# main.net
KiCad netlist of a schematic drawn in EAGLE
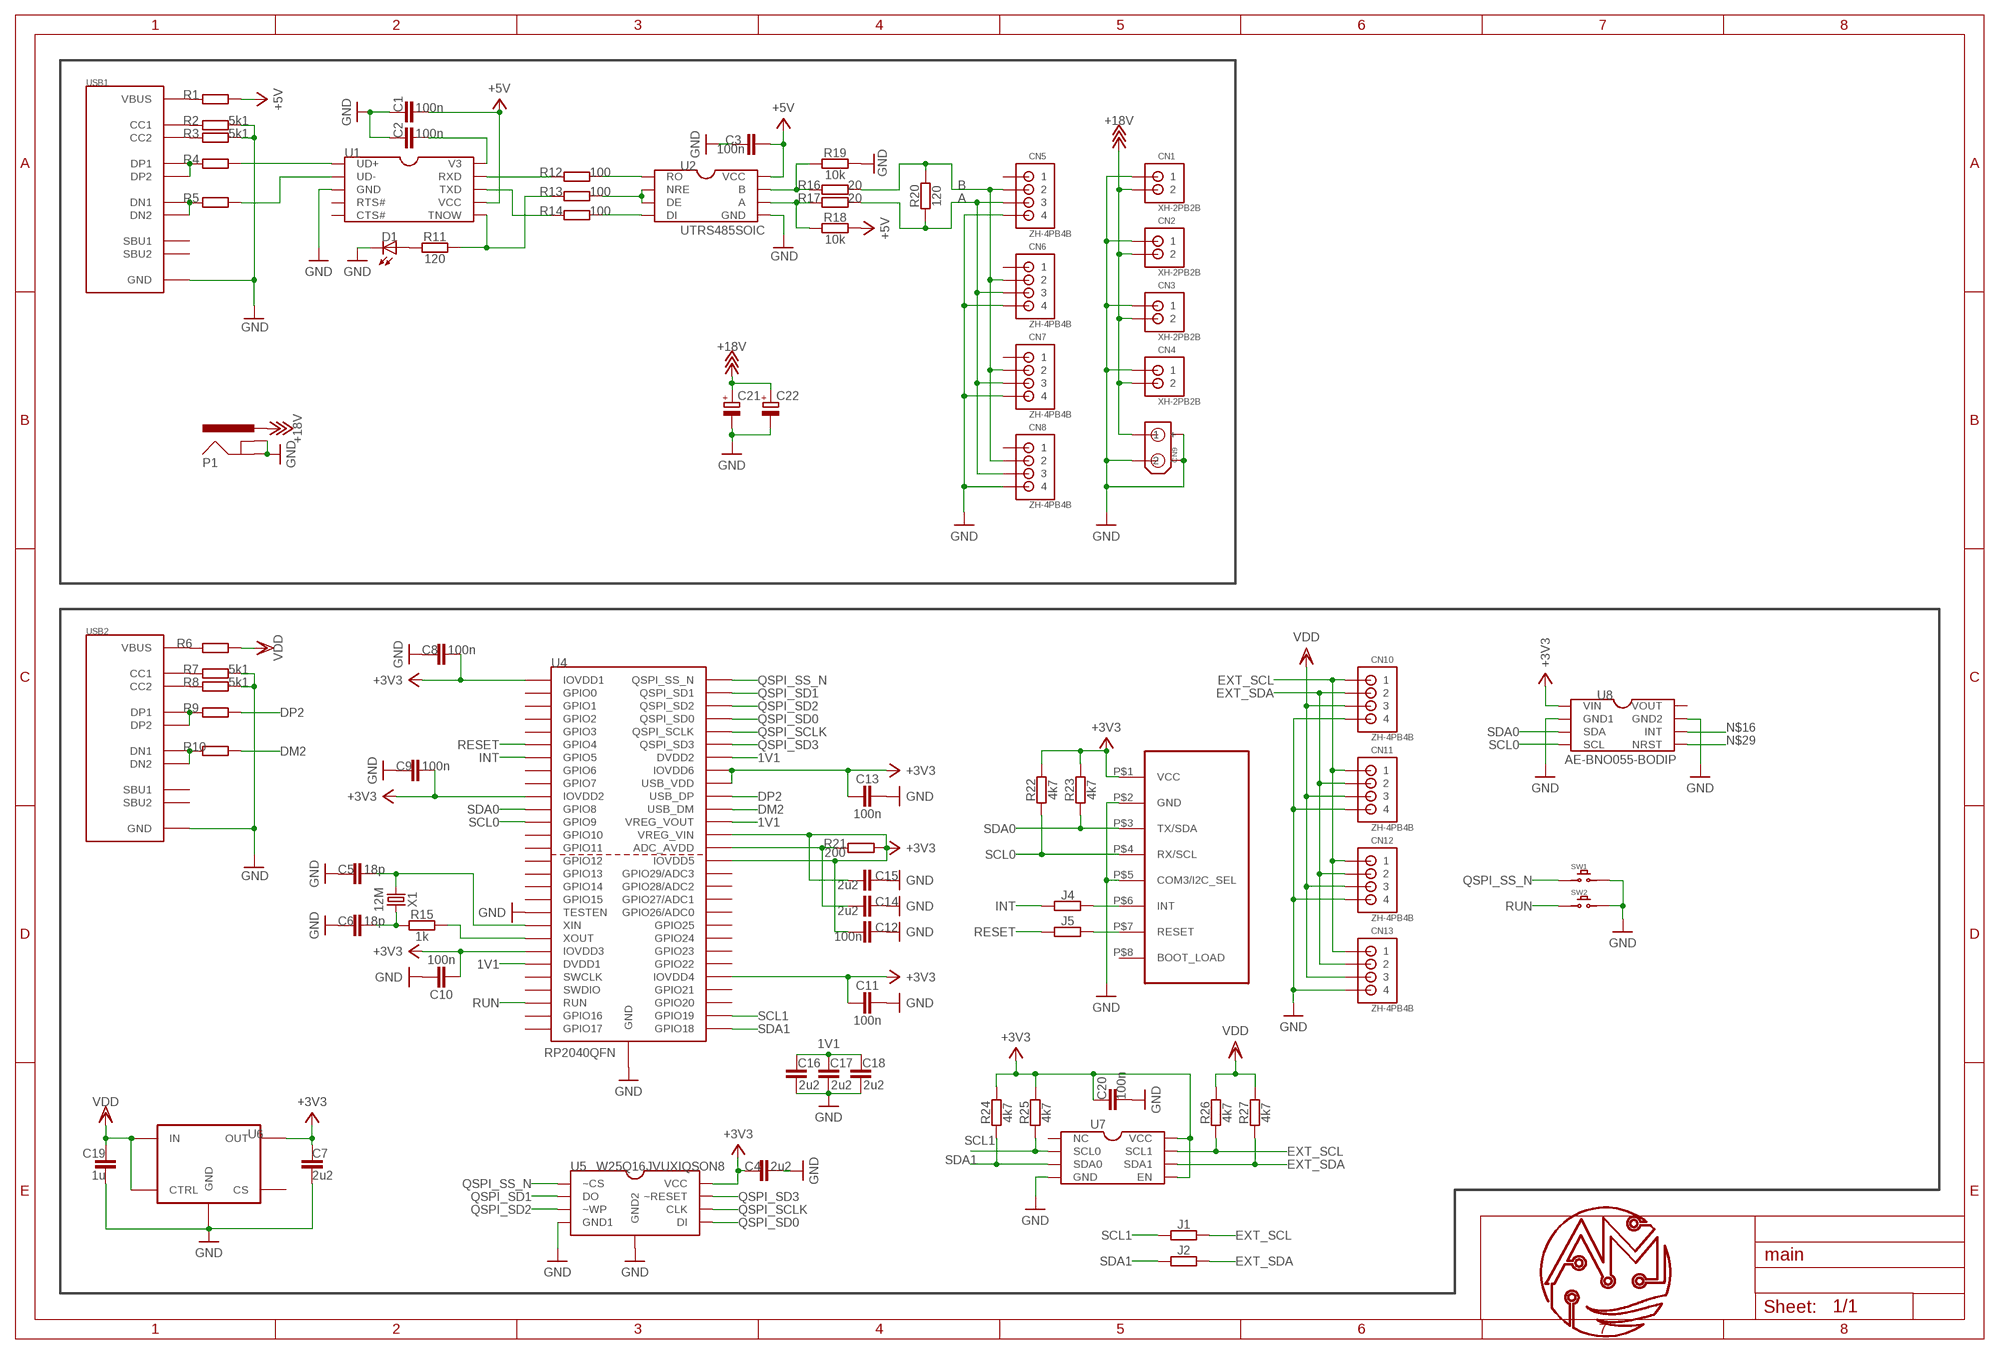
[diagram p0: schematic, sheet 1]

(export (version "E")
  (design (tool "Eeschema 10.0.6"))
  (components
    (comp (ref "C1")
      (value "100n")
      (footprint "eagle-import:C1608")
      (libsource (lib "eagle-import") (part "CAPACITOR1608"))
    )
    (comp (ref "C2")
      (value "100n")
      (footprint "eagle-import:C1608")
      (libsource (lib "eagle-import") (part "CAPACITOR1608"))
    )
    (comp (ref "C3")
      (value "100n")
      (footprint "eagle-import:C1608")
      (libsource (lib "eagle-import") (part "CAPACITOR1608"))
    )
    (comp (ref "C4")
      (value "2u2")
      (footprint "eagle-import:C1608")
      (libsource (lib "eagle-import") (part "CAPACITOR1608"))
    )
    (comp (ref "C5")
      (value "18p")
      (footprint "eagle-import:C1608")
      (libsource (lib "eagle-import") (part "CAPACITOR1608"))
    )
    (comp (ref "C6")
      (value "18p")
      (footprint "eagle-import:C1608")
      (libsource (lib "eagle-import") (part "CAPACITOR1608"))
    )
    (comp (ref "C7")
      (value "2u2")
      (footprint "eagle-import:C1608")
      (libsource (lib "eagle-import") (part "CAPACITOR1608"))
    )
    (comp (ref "C8")
      (value "100n")
      (footprint "eagle-import:C1608")
      (libsource (lib "eagle-import") (part "CAPACITOR1608"))
    )
    (comp (ref "C9")
      (value "100n")
      (footprint "eagle-import:C1608")
      (libsource (lib "eagle-import") (part "CAPACITOR1608"))
    )
    (comp (ref "C10")
      (value "100n")
      (footprint "eagle-import:C1608")
      (libsource (lib "eagle-import") (part "CAPACITOR1608"))
    )
    (comp (ref "C11")
      (value "100n")
      (footprint "eagle-import:C1608")
      (libsource (lib "eagle-import") (part "CAPACITOR1608"))
    )
    (comp (ref "C12")
      (value "100n")
      (footprint "eagle-import:C1608")
      (libsource (lib "eagle-import") (part "CAPACITOR1608"))
    )
    (comp (ref "C13")
      (value "100n")
      (footprint "eagle-import:C1608")
      (libsource (lib "eagle-import") (part "CAPACITOR1608"))
    )
    (comp (ref "C14")
      (value "2u2")
      (footprint "eagle-import:C1608")
      (libsource (lib "eagle-import") (part "CAPACITOR1608"))
    )
    (comp (ref "C15")
      (value "2u2")
      (footprint "eagle-import:C1608")
      (libsource (lib "eagle-import") (part "CAPACITOR1608"))
    )
    (comp (ref "C16")
      (value "2u2")
      (footprint "eagle-import:C1608")
      (libsource (lib "eagle-import") (part "CAPACITOR1608"))
    )
    (comp (ref "C17")
      (value "2u2")
      (footprint "eagle-import:C1608")
      (libsource (lib "eagle-import") (part "CAPACITOR1608"))
    )
    (comp (ref "C18")
      (value "2u2")
      (footprint "eagle-import:C1608")
      (libsource (lib "eagle-import") (part "CAPACITOR1608"))
    )
    (comp (ref "C19")
      (value "1u")
      (footprint "eagle-import:C1608")
      (libsource (lib "eagle-import") (part "CAPACITOR1608"))
    )
    (comp (ref "C20")
      (value "100n")
      (footprint "eagle-import:C1608")
      (libsource (lib "eagle-import") (part "CAPACITOR1608"))
    )
    (comp (ref "C21")
      (value "E_CAPACITORRADIAL_D8")
      (footprint "eagle-import:ECAP-D80-L115")
      (libsource (lib "eagle-import") (part "E_CAPACITORRADIAL_D8"))
    )
    (comp (ref "C22")
      (value "E_CAPACITORRADIAL_D8")
      (footprint "eagle-import:ECAP-D80-L115")
      (libsource (lib "eagle-import") (part "E_CAPACITORRADIAL_D8"))
    )
    (comp (ref "CN1")
      (value "XH-2PB2B")
      (footprint "eagle-import:B2B-XH-A")
      (libsource (lib "eagle-import") (part "XH-2PB2B"))
    )
    (comp (ref "CN2")
      (value "XH-2PB2B")
      (footprint "eagle-import:B2B-XH-A")
      (libsource (lib "eagle-import") (part "XH-2PB2B"))
    )
    (comp (ref "CN3")
      (value "XH-2PB2B")
      (footprint "eagle-import:B2B-XH-A")
      (libsource (lib "eagle-import") (part "XH-2PB2B"))
    )
    (comp (ref "CN4")
      (value "XH-2PB2B")
      (footprint "eagle-import:B2B-XH-A")
      (libsource (lib "eagle-import") (part "XH-2PB2B"))
    )
    (comp (ref "CN5")
      (value "ZH-4PB4B")
      (footprint "eagle-import:B4B-ZR")
      (libsource (lib "eagle-import") (part "ZH-4PB4B"))
    )
    (comp (ref "CN6")
      (value "ZH-4PB4B")
      (footprint "eagle-import:B4B-ZR")
      (libsource (lib "eagle-import") (part "ZH-4PB4B"))
    )
    (comp (ref "CN7")
      (value "ZH-4PB4B")
      (footprint "eagle-import:B4B-ZR")
      (libsource (lib "eagle-import") (part "ZH-4PB4B"))
    )
    (comp (ref "CN8")
      (value "ZH-4PB4B")
      (footprint "eagle-import:B4B-ZR")
      (libsource (lib "eagle-import") (part "ZH-4PB4B"))
    )
    (comp (ref "CN9")
      (value "XT60PW-MPCB")
      (footprint "eagle-import:XT60PW-M")
      (libsource (lib "eagle-import") (part "XT60PW-MPCB"))
    )
    (comp (ref "CN10")
      (value "ZH-4PB4B")
      (footprint "eagle-import:B4B-ZR")
      (libsource (lib "eagle-import") (part "ZH-4PB4B"))
    )
    (comp (ref "CN11")
      (value "ZH-4PB4B")
      (footprint "eagle-import:B4B-ZR")
      (libsource (lib "eagle-import") (part "ZH-4PB4B"))
    )
    (comp (ref "CN12")
      (value "ZH-4PB4B")
      (footprint "eagle-import:B4B-ZR")
      (libsource (lib "eagle-import") (part "ZH-4PB4B"))
    )
    (comp (ref "CN13")
      (value "ZH-4PB4B")
      (footprint "eagle-import:B4B-ZR")
      (libsource (lib "eagle-import") (part "ZH-4PB4B"))
    )
    (comp (ref "D1")
      (value "LED1608R")
      (footprint "eagle-import:LED1608R")
      (libsource (lib "eagle-import") (part "LED1608R"))
    )
    (comp (ref "J1")
      (value "JUMPER1608")
      (footprint "eagle-import:J1608")
      (libsource (lib "eagle-import") (part "JUMPER1608"))
    )
    (comp (ref "J2")
      (value "JUMPER1608")
      (footprint "eagle-import:J1608")
      (libsource (lib "eagle-import") (part "JUMPER1608"))
    )
    (comp (ref "J4")
      (value "JUMPER1608")
      (footprint "eagle-import:J1608")
      (libsource (lib "eagle-import") (part "JUMPER1608"))
    )
    (comp (ref "J5")
      (value "JUMPER1608")
      (footprint "eagle-import:J1608")
      (libsource (lib "eagle-import") (part "JUMPER1608"))
    )
    (comp (ref "P1")
      (value "DC-JACKMJ179PH")
      (footprint "eagle-import:MJ179PH")
      (libsource (lib "eagle-import") (part "DC-JACKMJ179PH"))
    )
    (comp (ref "R1")
      (value "RESISTER3225")
      (footprint "eagle-import:R3225")
      (libsource (lib "eagle-import") (part "RESISTER3225"))
    )
    (comp (ref "R2")
      (value "5k1")
      (footprint "eagle-import:R1608")
      (libsource (lib "eagle-import") (part "RESISTER1608"))
    )
    (comp (ref "R3")
      (value "5k1")
      (footprint "eagle-import:R1608")
      (libsource (lib "eagle-import") (part "RESISTER1608"))
    )
    (comp (ref "R4")
      (value "RESISTER1608")
      (footprint "eagle-import:R1608")
      (libsource (lib "eagle-import") (part "RESISTER1608"))
    )
    (comp (ref "R5")
      (value "RESISTER1608")
      (footprint "eagle-import:R1608")
      (libsource (lib "eagle-import") (part "RESISTER1608"))
    )
    (comp (ref "R6")
      (value "RESISTER3225")
      (footprint "eagle-import:R3225")
      (libsource (lib "eagle-import") (part "RESISTER3225"))
    )
    (comp (ref "R7")
      (value "5k1")
      (footprint "eagle-import:R1608")
      (libsource (lib "eagle-import") (part "RESISTER1608"))
    )
    (comp (ref "R8")
      (value "5k1")
      (footprint "eagle-import:R1608")
      (libsource (lib "eagle-import") (part "RESISTER1608"))
    )
    (comp (ref "R9")
      (value "RESISTER1608")
      (footprint "eagle-import:R1608")
      (libsource (lib "eagle-import") (part "RESISTER1608"))
    )
    (comp (ref "R10")
      (value "RESISTER1608")
      (footprint "eagle-import:R1608")
      (libsource (lib "eagle-import") (part "RESISTER1608"))
    )
    (comp (ref "R11")
      (value "120")
      (footprint "eagle-import:R1608")
      (libsource (lib "eagle-import") (part "RESISTER1608"))
    )
    (comp (ref "R12")
      (value "100")
      (footprint "eagle-import:R1608")
      (libsource (lib "eagle-import") (part "RESISTER1608"))
    )
    (comp (ref "R13")
      (value "100")
      (footprint "eagle-import:R1608")
      (libsource (lib "eagle-import") (part "RESISTER1608"))
    )
    (comp (ref "R14")
      (value "100")
      (footprint "eagle-import:R1608")
      (libsource (lib "eagle-import") (part "RESISTER1608"))
    )
    (comp (ref "R15")
      (value "1k")
      (footprint "eagle-import:R1608")
      (libsource (lib "eagle-import") (part "RESISTER1608"))
    )
    (comp (ref "R16")
      (value "20")
      (footprint "eagle-import:R1608")
      (libsource (lib "eagle-import") (part "RESISTER1608"))
    )
    (comp (ref "R17")
      (value "20")
      (footprint "eagle-import:R1608")
      (libsource (lib "eagle-import") (part "RESISTER1608"))
    )
    (comp (ref "R18")
      (value "10k")
      (footprint "eagle-import:R1608")
      (libsource (lib "eagle-import") (part "RESISTER1608"))
    )
    (comp (ref "R19")
      (value "10k")
      (footprint "eagle-import:R1608")
      (libsource (lib "eagle-import") (part "RESISTER1608"))
    )
    (comp (ref "R20")
      (value "120")
      (footprint "eagle-import:R1608")
      (libsource (lib "eagle-import") (part "RESISTER1608"))
    )
    (comp (ref "R21")
      (value "200")
      (footprint "eagle-import:R1608")
      (libsource (lib "eagle-import") (part "RESISTER1608"))
    )
    (comp (ref "R22")
      (value "4k7")
      (footprint "eagle-import:R1608")
      (libsource (lib "eagle-import") (part "RESISTER1608"))
    )
    (comp (ref "R23")
      (value "4k7")
      (footprint "eagle-import:R1608")
      (libsource (lib "eagle-import") (part "RESISTER1608"))
    )
    (comp (ref "R24")
      (value "4k7")
      (footprint "eagle-import:R1608")
      (libsource (lib "eagle-import") (part "RESISTER1608"))
    )
    (comp (ref "R25")
      (value "4k7")
      (footprint "eagle-import:R1608")
      (libsource (lib "eagle-import") (part "RESISTER1608"))
    )
    (comp (ref "R26")
      (value "4k7")
      (footprint "eagle-import:R1608")
      (libsource (lib "eagle-import") (part "RESISTER1608"))
    )
    (comp (ref "R27")
      (value "4k7")
      (footprint "eagle-import:R1608")
      (libsource (lib "eagle-import") (part "RESISTER1608"))
    )
    (comp (ref "SW1")
      (value "TSY3420SMD-HOLE")
      (footprint "eagle-import:TSY3420-HOLE")
      (libsource (lib "eagle-import") (part "TSY3420SMD-HOLE"))
    )
    (comp (ref "SW2")
      (value "TSY3420SMD-HOLE")
      (footprint "eagle-import:TSY3420-HOLE")
      (libsource (lib "eagle-import") (part "TSY3420SMD-HOLE"))
    )
    (comp (ref "U$2")
      (value "LOGO8MM")
      (footprint "eagle-import:LOGO-8MM")
      (libsource (lib "eagle-import") (part "LOGO8MM"))
    )
    (comp (ref "U1")
      (value "CH340EMSOP")
      (footprint "eagle-import:MSOP-05-10P")
      (libsource (lib "eagle-import") (part "CH340EMSOP"))
    )
    (comp (ref "U2")
      (value "UTRS485SOIC")
      (footprint "eagle-import:SOIC-8P")
      (libsource (lib "eagle-import") (part "UTRS485SOIC"))
    )
    (comp (ref "U3")
      (value "CJMCU-055SIP")
      (footprint "eagle-import:CJMCU-055")
      (libsource (lib "eagle-import") (part "CJMCU-055SIP"))
    )
    (comp (ref "U4")
      (value "RP2040QFN")
      (footprint "eagle-import:RP2040")
      (libsource (lib "eagle-import") (part "RP2040QFN"))
    )
    (comp (ref "U5")
      (value "W25Q16JVUXIQSON8")
      (footprint "eagle-import:W25Q16JVUXIQ")
      (libsource (lib "eagle-import") (part "W25Q16JVUXIQSON8"))
    )
    (comp (ref "U6")
      (value "REGULATOR2SOT23-5P")
      (footprint "eagle-import:SOT23-5P")
      (libsource (lib "eagle-import") (part "REGULATOR2SOT23-5P"))
    )
    (comp (ref "U7")
      (value "PCA9515SOIC")
      (footprint "eagle-import:PCA9515-SOIC")
      (libsource (lib "eagle-import") (part "PCA9515SOIC"))
    )
    (comp (ref "U8")
      (value "AE-BNO055-BODIP")
      (footprint "eagle-import:AE-BNO055-BO")
      (libsource (lib "eagle-import") (part "AE-BNO055-BODIP"))
    )
    (comp (ref "USB1")
      (value "USB-CSMD")
      (footprint "eagle-import:5077CR-16-SMC2-BK-TR")
      (libsource (lib "eagle-import") (part "USB-CSMD"))
    )
    (comp (ref "USB2")
      (value "USB-CSMD")
      (footprint "eagle-import:5077CR-16-SMC2-BK-TR")
      (libsource (lib "eagle-import") (part "USB-CSMD"))
    )
    (comp (ref "X1")
      (value "12M")
      (footprint "eagle-import:HC49S")
      (libsource (lib "eagle-import") (part "XTALHC49S"))
    )
  )
  (nets
    (net (code "1") (name "+3V3") (class "Default")
      (node (ref "C10") (pin "P$2") (pinfunction "2_P$2") (pintype "passive"))
      (node (ref "C11") (pin "P$2") (pinfunction "2_P$2") (pintype "passive"))
      (node (ref "C12") (pin "P$2") (pinfunction "2_P$2") (pintype "passive"))
      (node (ref "C13") (pin "P$1") (pinfunction "1_P$1") (pintype "passive"))
      (node (ref "C15") (pin "P$2") (pinfunction "2_P$2") (pintype "passive"))
      (node (ref "C20") (pin "P$1") (pinfunction "1_P$1") (pintype "passive"))
      (node (ref "C4") (pin "P$1") (pinfunction "1_P$1") (pintype "passive"))
      (node (ref "C7") (pin "P$2") (pinfunction "2_P$2") (pintype "passive"))
      (node (ref "C8") (pin "P$2") (pinfunction "2_P$2") (pintype "passive"))
      (node (ref "C9") (pin "P$2") (pinfunction "2_P$2") (pintype "passive"))
      (node (ref "R21") (pin "P$2") (pinfunction "2_P$2") (pintype "passive"))
      (node (ref "R22") (pin "P$2") (pinfunction "2_P$2") (pintype "passive"))
      (node (ref "R23") (pin "P$2") (pinfunction "2_P$2") (pintype "passive"))
      (node (ref "R24") (pin "P$2") (pinfunction "2_P$2") (pintype "passive"))
      (node (ref "R25") (pin "P$2") (pinfunction "2_P$2") (pintype "passive"))
      (node (ref "U3") (pin "P$1") (pinfunction "VCC_P$1") (pintype "bidirectional"))
      (node (ref "U4") (pin "P$1") (pinfunction "IOVDD1_P$1") (pintype "bidirectional"))
      (node (ref "U4") (pin "P$10") (pinfunction "IOVDD2_P$10") (pintype "bidirectional"))
      (node (ref "U4") (pin "P$22") (pinfunction "IOVDD3_P$22") (pintype "bidirectional"))
      (node (ref "U4") (pin "P$33") (pinfunction "IOVDD4_P$33") (pintype "bidirectional"))
      (node (ref "U4") (pin "P$42") (pinfunction "IOVDD5_P$42") (pintype "bidirectional"))
      (node (ref "U4") (pin "P$44") (pinfunction "VREG_VIN_P$44") (pintype "bidirectional"))
      (node (ref "U4") (pin "P$48") (pinfunction "USB_VDD_P$48") (pintype "bidirectional"))
      (node (ref "U4") (pin "P$49") (pinfunction "IOVDD6_P$49") (pintype "bidirectional"))
      (node (ref "U5") (pin "P$8") (pinfunction "VCC_P$8") (pintype "passive"))
      (node (ref "U6") (pin "P$5") (pinfunction "OUT_P$5") (pintype "passive"))
      (node (ref "U7") (pin "P$5") (pinfunction "EN_P$5") (pintype "passive"))
      (node (ref "U7") (pin "P$8") (pinfunction "VCC_P$8") (pintype "passive"))
      (node (ref "U8") (pin "P$1") (pinfunction "VIN_P$1") (pintype "passive"))
    )
    (net (code "2") (name "+5V") (class "Default")
      (node (ref "C1") (pin "P$2") (pinfunction "2_P$2") (pintype "passive"))
      (node (ref "C3") (pin "P$1") (pinfunction "1_P$1") (pintype "passive"))
      (node (ref "R1") (pin "P$2") (pinfunction "2_P$2") (pintype "passive"))
      (node (ref "R18") (pin "P$1") (pinfunction "1_P$1") (pintype "passive"))
      (node (ref "U1") (pin "P$7") (pinfunction "VCC_P$7") (pintype "passive"))
      (node (ref "U2") (pin "P$8") (pinfunction "VCC_P$8") (pintype "passive"))
    )
    (net (code "3") (name "+18V") (class "Default")
      (node (ref "C21") (pin "+") (pinfunction "+_+") (pintype "passive"))
      (node (ref "C22") (pin "+") (pinfunction "+_+") (pintype "passive"))
      (node (ref "CN1") (pin "2") (pinfunction "2_2") (pintype "bidirectional"))
      (node (ref "CN2") (pin "2") (pinfunction "2_2") (pintype "bidirectional"))
      (node (ref "CN3") (pin "2") (pinfunction "2_2") (pintype "bidirectional"))
      (node (ref "CN4") (pin "2") (pinfunction "2_2") (pintype "bidirectional"))
      (node (ref "CN9") (pin "P$1") (pinfunction "+_P$1") (pintype "bidirectional"))
      (node (ref "P1") (pin "VCC") (pinfunction "PWR_VCC") (pintype "bidirectional"))
      (node (ref "P1") (pin "VCC1") (pinfunction "PWR_VCC1") (pintype "bidirectional"))
    )
    (net (code "4") (name "/1V1") (class "Default")
      (node (ref "C16") (pin "P$1") (pinfunction "1_P$1") (pintype "passive"))
      (node (ref "C17") (pin "P$1") (pinfunction "1_P$1") (pintype "passive"))
      (node (ref "C18") (pin "P$1") (pinfunction "1_P$1") (pintype "passive"))
      (node (ref "U4") (pin "P$23") (pinfunction "DVDD1_P$23") (pintype "bidirectional"))
      (node (ref "U4") (pin "P$45") (pinfunction "VREG_VOUT_P$45") (pintype "bidirectional"))
      (node (ref "U4") (pin "P$50") (pinfunction "DVDD2_P$50") (pintype "bidirectional"))
    )
    (net (code "5") (name "/A") (class "Default")
      (node (ref "CN5") (pin "3") (pinfunction "3_3") (pintype "bidirectional"))
      (node (ref "CN6") (pin "3") (pinfunction "3_3") (pintype "bidirectional"))
      (node (ref "CN7") (pin "3") (pinfunction "3_3") (pintype "bidirectional"))
      (node (ref "CN8") (pin "3") (pinfunction "3_3") (pintype "bidirectional"))
      (node (ref "R17") (pin "P$1") (pinfunction "1_P$1") (pintype "passive"))
      (node (ref "R20") (pin "P$2") (pinfunction "2_P$2") (pintype "passive"))
    )
    (net (code "6") (name "/B") (class "Default")
      (node (ref "CN5") (pin "2") (pinfunction "2_2") (pintype "bidirectional"))
      (node (ref "CN6") (pin "2") (pinfunction "2_2") (pintype "bidirectional"))
      (node (ref "CN7") (pin "2") (pinfunction "2_2") (pintype "bidirectional"))
      (node (ref "CN8") (pin "2") (pinfunction "2_2") (pintype "bidirectional"))
      (node (ref "R16") (pin "P$1") (pinfunction "1_P$1") (pintype "passive"))
      (node (ref "R20") (pin "P$1") (pinfunction "1_P$1") (pintype "passive"))
    )
    (net (code "7") (name "/DM2") (class "Default")
      (node (ref "R10") (pin "P$2") (pinfunction "2_P$2") (pintype "passive"))
      (node (ref "U4") (pin "P$46") (pinfunction "USB_DM_P$46") (pintype "bidirectional"))
    )
    (net (code "8") (name "/DP2") (class "Default")
      (node (ref "R9") (pin "P$2") (pinfunction "2_P$2") (pintype "passive"))
      (node (ref "U4") (pin "P$47") (pinfunction "USB_DP_P$47") (pintype "bidirectional"))
    )
    (net (code "9") (name "/EXT_SCL") (class "Default")
      (node (ref "CN10") (pin "1") (pinfunction "1_1") (pintype "bidirectional"))
      (node (ref "CN11") (pin "1") (pinfunction "1_1") (pintype "bidirectional"))
      (node (ref "CN12") (pin "1") (pinfunction "1_1") (pintype "bidirectional"))
      (node (ref "CN13") (pin "1") (pinfunction "1_1") (pintype "bidirectional"))
      (node (ref "J1") (pin "P$2") (pinfunction "2_P$2") (pintype "passive"))
      (node (ref "R26") (pin "P$1") (pinfunction "1_P$1") (pintype "passive"))
      (node (ref "U7") (pin "P$7") (pinfunction "SCL1_P$7") (pintype "passive"))
    )
    (net (code "10") (name "/EXT_SDA") (class "Default")
      (node (ref "CN10") (pin "2") (pinfunction "2_2") (pintype "bidirectional"))
      (node (ref "CN11") (pin "2") (pinfunction "2_2") (pintype "bidirectional"))
      (node (ref "CN12") (pin "2") (pinfunction "2_2") (pintype "bidirectional"))
      (node (ref "CN13") (pin "2") (pinfunction "2_2") (pintype "bidirectional"))
      (node (ref "J2") (pin "P$2") (pinfunction "2_P$2") (pintype "passive"))
      (node (ref "R27") (pin "P$1") (pinfunction "1_P$1") (pintype "passive"))
      (node (ref "U7") (pin "P$6") (pinfunction "SDA1_P$6") (pintype "passive"))
    )
    (net (code "11") (name "/INT") (class "Default")
      (node (ref "J4") (pin "P$1") (pinfunction "1_P$1") (pintype "passive"))
      (node (ref "U4") (pin "P$7") (pinfunction "GPIO5_P$7") (pintype "bidirectional"))
    )
    (net (code "12") (name "/N$16") (class "Default")
      (node (ref "J4") (pin "P$2") (pinfunction "2_P$2") (pintype "passive"))
      (node (ref "U3") (pin "P$6") (pinfunction "INT_P$6") (pintype "bidirectional"))
      (node (ref "U8") (pin "P$6") (pinfunction "INT_P$6") (pintype "passive"))
    )
    (net (code "13") (name "/N$29") (class "Default")
      (node (ref "J5") (pin "P$2") (pinfunction "2_P$2") (pintype "passive"))
      (node (ref "U3") (pin "P$7") (pinfunction "RESET_P$7") (pintype "bidirectional"))
      (node (ref "U8") (pin "P$5") (pinfunction "NRST_P$5") (pintype "passive"))
    )
    (net (code "14") (name "/QSPI_SCLK") (class "Default")
      (node (ref "U4") (pin "P$52") (pinfunction "QSPI_SCLK_P$52") (pintype "bidirectional"))
      (node (ref "U5") (pin "P$6") (pinfunction "CLK_P$6") (pintype "passive"))
    )
    (net (code "15") (name "/QSPI_SD0") (class "Default")
      (node (ref "U4") (pin "P$53") (pinfunction "QSPI_SD0_P$53") (pintype "bidirectional"))
      (node (ref "U5") (pin "P$5") (pinfunction "DI_P$5") (pintype "passive"))
    )
    (net (code "16") (name "/QSPI_SD1") (class "Default")
      (node (ref "U4") (pin "P$55") (pinfunction "QSPI_SD1_P$55") (pintype "bidirectional"))
      (node (ref "U5") (pin "P$2") (pinfunction "DO_P$2") (pintype "passive"))
    )
    (net (code "17") (name "/QSPI_SD2") (class "Default")
      (node (ref "U4") (pin "P$54") (pinfunction "QSPI_SD2_P$54") (pintype "bidirectional"))
      (node (ref "U5") (pin "P$3") (pinfunction "~{WP}_P$3") (pintype "passive"))
    )
    (net (code "18") (name "/QSPI_SD3") (class "Default")
      (node (ref "U4") (pin "P$51") (pinfunction "QSPI_SD3_P$51") (pintype "bidirectional"))
      (node (ref "U5") (pin "P$7") (pinfunction "~{RESET}_P$7") (pintype "passive"))
    )
    (net (code "19") (name "/QSPI_SS_N") (class "Default")
      (node (ref "SW1") (pin "P$1") (pinfunction "P$1_P$1") (pintype "bidirectional"))
      (node (ref "U4") (pin "P$56") (pinfunction "QSPI_SS_N_P$56") (pintype "bidirectional"))
      (node (ref "U5") (pin "P$1") (pinfunction "~{CS}_P$1") (pintype "passive"))
    )
    (net (code "20") (name "/RESET") (class "Default")
      (node (ref "J5") (pin "P$1") (pinfunction "1_P$1") (pintype "passive"))
      (node (ref "U4") (pin "P$6") (pinfunction "GPIO4_P$6") (pintype "bidirectional"))
    )
    (net (code "21") (name "/RUN") (class "Default")
      (node (ref "SW2") (pin "P$1") (pinfunction "P$1_P$1") (pintype "bidirectional"))
      (node (ref "U4") (pin "P$26") (pinfunction "RUN_P$26") (pintype "bidirectional"))
    )
    (net (code "22") (name "/SCL0") (class "Default")
      (node (ref "R22") (pin "P$1") (pinfunction "1_P$1") (pintype "passive"))
      (node (ref "U3") (pin "P$4") (pinfunction "RX/SCL_P$4") (pintype "bidirectional"))
      (node (ref "U4") (pin "P$12") (pinfunction "GPIO9_P$12") (pintype "bidirectional"))
      (node (ref "U8") (pin "P$4") (pinfunction "SCL_P$4") (pintype "passive"))
    )
    (net (code "23") (name "/SCL1") (class "Default")
      (node (ref "J1") (pin "P$1") (pinfunction "1_P$1") (pintype "passive"))
      (node (ref "R25") (pin "P$1") (pinfunction "1_P$1") (pintype "passive"))
      (node (ref "U4") (pin "P$30") (pinfunction "GPIO19_P$30") (pintype "bidirectional"))
      (node (ref "U7") (pin "P$2") (pinfunction "SCL0_P$2") (pintype "passive"))
    )
    (net (code "24") (name "/SDA0") (class "Default")
      (node (ref "R23") (pin "P$1") (pinfunction "1_P$1") (pintype "passive"))
      (node (ref "U3") (pin "P$3") (pinfunction "TX/SDA_P$3") (pintype "bidirectional"))
      (node (ref "U4") (pin "P$11") (pinfunction "GPIO8_P$11") (pintype "bidirectional"))
      (node (ref "U8") (pin "P$3") (pinfunction "SDA_P$3") (pintype "passive"))
    )
    (net (code "25") (name "/SDA1") (class "Default")
      (node (ref "J2") (pin "P$1") (pinfunction "1_P$1") (pintype "passive"))
      (node (ref "R24") (pin "P$1") (pinfunction "1_P$1") (pintype "passive"))
      (node (ref "U4") (pin "P$29") (pinfunction "GPIO18_P$29") (pintype "bidirectional"))
      (node (ref "U7") (pin "P$3") (pinfunction "SDA0_P$3") (pintype "passive"))
    )
    (net (code "26") (name "GND") (class "Default")
      (node (ref "C1") (pin "P$1") (pinfunction "1_P$1") (pintype "passive"))
      (node (ref "C10") (pin "P$1") (pinfunction "1_P$1") (pintype "passive"))
      (node (ref "C11") (pin "P$1") (pinfunction "1_P$1") (pintype "passive"))
      (node (ref "C12") (pin "P$1") (pinfunction "1_P$1") (pintype "passive"))
      (node (ref "C13") (pin "P$2") (pinfunction "2_P$2") (pintype "passive"))
      (node (ref "C14") (pin "P$1") (pinfunction "1_P$1") (pintype "passive"))
      (node (ref "C15") (pin "P$1") (pinfunction "1_P$1") (pintype "passive"))
      (node (ref "C16") (pin "P$2") (pinfunction "2_P$2") (pintype "passive"))
      (node (ref "C17") (pin "P$2") (pinfunction "2_P$2") (pintype "passive"))
      (node (ref "C18") (pin "P$2") (pinfunction "2_P$2") (pintype "passive"))
      (node (ref "C19") (pin "P$1") (pinfunction "1_P$1") (pintype "passive"))
      (node (ref "C2") (pin "P$1") (pinfunction "1_P$1") (pintype "passive"))
      (node (ref "C20") (pin "P$2") (pinfunction "2_P$2") (pintype "passive"))
      (node (ref "C21") (pin "-") (pinfunction "-_-") (pintype "passive"))
      (node (ref "C22") (pin "-") (pinfunction "-_-") (pintype "passive"))
      (node (ref "C3") (pin "P$2") (pinfunction "2_P$2") (pintype "passive"))
      (node (ref "C4") (pin "P$2") (pinfunction "2_P$2") (pintype "passive"))
      (node (ref "C5") (pin "P$1") (pinfunction "1_P$1") (pintype "passive"))
      (node (ref "C6") (pin "P$1") (pinfunction "1_P$1") (pintype "passive"))
      (node (ref "C7") (pin "P$1") (pinfunction "1_P$1") (pintype "passive"))
      (node (ref "C8") (pin "P$1") (pinfunction "1_P$1") (pintype "passive"))
      (node (ref "C9") (pin "P$1") (pinfunction "1_P$1") (pintype "passive"))
      (node (ref "CN1") (pin "1") (pinfunction "1_1") (pintype "bidirectional"))
      (node (ref "CN10") (pin "4") (pinfunction "4_4") (pintype "bidirectional"))
      (node (ref "CN11") (pin "4") (pinfunction "4_4") (pintype "bidirectional"))
      (node (ref "CN12") (pin "4") (pinfunction "4_4") (pintype "bidirectional"))
      (node (ref "CN13") (pin "4") (pinfunction "4_4") (pintype "bidirectional"))
      (node (ref "CN2") (pin "1") (pinfunction "1_1") (pintype "bidirectional"))
      (node (ref "CN3") (pin "1") (pinfunction "1_1") (pintype "bidirectional"))
      (node (ref "CN4") (pin "1") (pinfunction "1_1") (pintype "bidirectional"))
      (node (ref "CN5") (pin "4") (pinfunction "4_4") (pintype "bidirectional"))
      (node (ref "CN6") (pin "4") (pinfunction "4_4") (pintype "bidirectional"))
      (node (ref "CN7") (pin "4") (pinfunction "4_4") (pintype "bidirectional"))
      (node (ref "CN8") (pin "4") (pinfunction "4_4") (pintype "bidirectional"))
      (node (ref "CN9") (pin "P$2") (pinfunction "-_P$2") (pintype "bidirectional"))
      (node (ref "CN9") (pin "P$3") (pinfunction "-1_P$3") (pintype "bidirectional"))
      (node (ref "CN9") (pin "P$4") (pinfunction "-2_P$4") (pintype "bidirectional"))
      (node (ref "CN9") (pin "P$5") (pinfunction "-1_P$5") (pintype "bidirectional"))
      (node (ref "CN9") (pin "P$6") (pinfunction "-2_P$6") (pintype "bidirectional"))
      (node (ref "D1") (pin "P$2") (pinfunction "K_P$2") (pintype "passive"))
      (node (ref "P1") (pin "BREAK") (pinfunction "GNDBREAK_BREAK") (pintype "bidirectional"))
      (node (ref "P1") (pin "BREAK1") (pinfunction "GNDBREAK_BREAK1") (pintype "bidirectional"))
      (node (ref "P1") (pin "GND") (pinfunction "GND_GND") (pintype "bidirectional"))
      (node (ref "P1") (pin "GND1") (pinfunction "GND_GND1") (pintype "bidirectional"))
      (node (ref "R19") (pin "P$1") (pinfunction "1_P$1") (pintype "passive"))
      (node (ref "R2") (pin "P$2") (pinfunction "2_P$2") (pintype "passive"))
      (node (ref "R3") (pin "P$2") (pinfunction "2_P$2") (pintype "passive"))
      (node (ref "R7") (pin "P$2") (pinfunction "2_P$2") (pintype "passive"))
      (node (ref "R8") (pin "P$2") (pinfunction "2_P$2") (pintype "passive"))
      (node (ref "SW1") (pin "P$2") (pinfunction "P$2_P$2") (pintype "bidirectional"))
      (node (ref "SW2") (pin "P$2") (pinfunction "P$2_P$2") (pintype "bidirectional"))
      (node (ref "U1") (pin "P$3") (pinfunction "GND_P$3") (pintype "passive"))
      (node (ref "U2") (pin "P$5") (pinfunction "GND_P$5") (pintype "passive"))
      (node (ref "U3") (pin "P$2") (pinfunction "GND_P$2") (pintype "bidirectional"))
      (node (ref "U3") (pin "P$5") (pinfunction "COM3/I2C_SEL_P$5") (pintype "bidirectional"))
      (node (ref "U4") (pin "P$19") (pinfunction "TESTEN_P$19") (pintype "bidirectional"))
      (node (ref "U4") (pin "P$57") (pinfunction "GND_P$57") (pintype "bidirectional"))
      (node (ref "U5") (pin "P$4") (pinfunction "GND1_P$4") (pintype "passive"))
      (node (ref "U5") (pin "P$9") (pinfunction "GND2_P$9") (pintype "passive"))
      (node (ref "U6") (pin "P$2") (pinfunction "GND_P$2") (pintype "input"))
      (node (ref "U7") (pin "P$4") (pinfunction "GND_P$4") (pintype "passive"))
      (node (ref "U8") (pin "P$2") (pinfunction "GND1_P$2") (pintype "passive"))
      (node (ref "U8") (pin "P$7") (pinfunction "GND2_P$7") (pintype "passive"))
      (node (ref "USB1") (pin "A1_B12") (pinfunction "GND_A1_B12") (pintype "bidirectional"))
      (node (ref "USB1") (pin "B1_A12") (pinfunction "GND_B1_A12") (pintype "bidirectional"))
      (node (ref "USB1") (pin "P$13") (pinfunction "GND_P$13") (pintype "bidirectional"))
      (node (ref "USB1") (pin "P$14") (pinfunction "GND_P$14") (pintype "bidirectional"))
      (node (ref "USB1") (pin "P$15") (pinfunction "GND_P$15") (pintype "bidirectional"))
      (node (ref "USB1") (pin "P$16") (pinfunction "GND_P$16") (pintype "bidirectional"))
      (node (ref "USB1") (pin "P$17") (pinfunction "GND_P$17") (pintype "bidirectional"))
      (node (ref "USB1") (pin "P$18") (pinfunction "GND_P$18") (pintype "bidirectional"))
      (node (ref "USB1") (pin "P$19") (pinfunction "GND_P$19") (pintype "bidirectional"))
      (node (ref "USB1") (pin "P$20") (pinfunction "GND_P$20") (pintype "bidirectional"))
      (node (ref "USB2") (pin "A1_B12") (pinfunction "GND_A1_B12") (pintype "bidirectional"))
      (node (ref "USB2") (pin "B1_A12") (pinfunction "GND_B1_A12") (pintype "bidirectional"))
      (node (ref "USB2") (pin "P$13") (pinfunction "GND_P$13") (pintype "bidirectional"))
      (node (ref "USB2") (pin "P$14") (pinfunction "GND_P$14") (pintype "bidirectional"))
      (node (ref "USB2") (pin "P$15") (pinfunction "GND_P$15") (pintype "bidirectional"))
      (node (ref "USB2") (pin "P$16") (pinfunction "GND_P$16") (pintype "bidirectional"))
      (node (ref "USB2") (pin "P$17") (pinfunction "GND_P$17") (pintype "bidirectional"))
      (node (ref "USB2") (pin "P$18") (pinfunction "GND_P$18") (pintype "bidirectional"))
      (node (ref "USB2") (pin "P$19") (pinfunction "GND_P$19") (pintype "bidirectional"))
      (node (ref "USB2") (pin "P$20") (pinfunction "GND_P$20") (pintype "bidirectional"))
    )
    (net (code "27") (name "Net-(C2-2)") (class "Default")
      (node (ref "C2") (pin "P$2") (pinfunction "2_P$2") (pintype "passive"))
      (node (ref "U1") (pin "P$10") (pinfunction "V3_P$10") (pintype "passive"))
    )
    (net (code "28") (name "Net-(C5-2)") (class "Default")
      (node (ref "C5") (pin "P$2") (pinfunction "2_P$2") (pintype "passive"))
      (node (ref "U4") (pin "P$20") (pinfunction "XIN_P$20") (pintype "bidirectional"))
      (node (ref "X1") (pin "2") (pinfunction "2_2") (pintype "passive"))
    )
    (net (code "29") (name "Net-(C6-2)") (class "Default")
      (node (ref "C6") (pin "P$2") (pinfunction "2_P$2") (pintype "passive"))
      (node (ref "R15") (pin "P$1") (pinfunction "1_P$1") (pintype "passive"))
      (node (ref "X1") (pin "1") (pinfunction "1_1") (pintype "passive"))
    )
    (net (code "30") (name "Net-(C14-2)") (class "Default")
      (node (ref "C14") (pin "P$2") (pinfunction "2_P$2") (pintype "passive"))
      (node (ref "R21") (pin "P$1") (pinfunction "1_P$1") (pintype "passive"))
      (node (ref "U4") (pin "P$43") (pinfunction "ADC_AVDD_P$43") (pintype "bidirectional"))
    )
    (net (code "31") (name "Net-(D1-A)") (class "Default")
      (node (ref "D1") (pin "P$1") (pinfunction "A_P$1") (pintype "passive"))
      (node (ref "R11") (pin "P$2") (pinfunction "2_P$2") (pintype "passive"))
    )
    (net (code "32") (name "Net-(R1-1)") (class "Default")
      (node (ref "R1") (pin "P$1") (pinfunction "1_P$1") (pintype "passive"))
      (node (ref "USB1") (pin "A4_B9") (pinfunction "VBUS_A4_B9") (pintype "bidirectional"))
      (node (ref "USB1") (pin "B4_A9") (pinfunction "VBUS_B4_A9") (pintype "bidirectional"))
    )
    (net (code "33") (name "Net-(R2-1)") (class "Default")
      (node (ref "R2") (pin "P$1") (pinfunction "1_P$1") (pintype "passive"))
      (node (ref "USB1") (pin "A5") (pinfunction "CC1_A5") (pintype "bidirectional"))
    )
    (net (code "34") (name "Net-(R3-1)") (class "Default")
      (node (ref "R3") (pin "P$1") (pinfunction "1_P$1") (pintype "passive"))
      (node (ref "USB1") (pin "B5") (pinfunction "CC2_B5") (pintype "bidirectional"))
    )
    (net (code "35") (name "Net-(R4-1)") (class "Default")
      (node (ref "R4") (pin "P$1") (pinfunction "1_P$1") (pintype "passive"))
      (node (ref "USB1") (pin "A6") (pinfunction "DP1_A6") (pintype "bidirectional"))
      (node (ref "USB1") (pin "B6") (pinfunction "DP2_B6") (pintype "bidirectional"))
    )
    (net (code "36") (name "Net-(R4-2)") (class "Default")
      (node (ref "R4") (pin "P$2") (pinfunction "2_P$2") (pintype "passive"))
      (node (ref "U1") (pin "P$1") (pinfunction "UD+_P$1") (pintype "passive"))
    )
    (net (code "37") (name "Net-(R5-1)") (class "Default")
      (node (ref "R5") (pin "P$1") (pinfunction "1_P$1") (pintype "passive"))
      (node (ref "USB1") (pin "A7") (pinfunction "DN1_A7") (pintype "bidirectional"))
      (node (ref "USB1") (pin "B7") (pinfunction "DN2_B7") (pintype "bidirectional"))
    )
    (net (code "38") (name "Net-(R5-2)") (class "Default")
      (node (ref "R5") (pin "P$2") (pinfunction "2_P$2") (pintype "passive"))
      (node (ref "U1") (pin "P$2") (pinfunction "UD-_P$2") (pintype "passive"))
    )
    (net (code "39") (name "Net-(R6-1)") (class "Default")
      (node (ref "R6") (pin "P$1") (pinfunction "1_P$1") (pintype "passive"))
      (node (ref "USB2") (pin "A4_B9") (pinfunction "VBUS_A4_B9") (pintype "bidirectional"))
      (node (ref "USB2") (pin "B4_A9") (pinfunction "VBUS_B4_A9") (pintype "bidirectional"))
    )
    (net (code "40") (name "Net-(R7-1)") (class "Default")
      (node (ref "R7") (pin "P$1") (pinfunction "1_P$1") (pintype "passive"))
      (node (ref "USB2") (pin "A5") (pinfunction "CC1_A5") (pintype "bidirectional"))
    )
    (net (code "41") (name "Net-(R8-1)") (class "Default")
      (node (ref "R8") (pin "P$1") (pinfunction "1_P$1") (pintype "passive"))
      (node (ref "USB2") (pin "B5") (pinfunction "CC2_B5") (pintype "bidirectional"))
    )
    (net (code "42") (name "Net-(R9-1)") (class "Default")
      (node (ref "R9") (pin "P$1") (pinfunction "1_P$1") (pintype "passive"))
      (node (ref "USB2") (pin "A6") (pinfunction "DP1_A6") (pintype "bidirectional"))
      (node (ref "USB2") (pin "B6") (pinfunction "DP2_B6") (pintype "bidirectional"))
    )
    (net (code "43") (name "Net-(R10-1)") (class "Default")
      (node (ref "R10") (pin "P$1") (pinfunction "1_P$1") (pintype "passive"))
      (node (ref "USB2") (pin "A7") (pinfunction "DN1_A7") (pintype "bidirectional"))
      (node (ref "USB2") (pin "B7") (pinfunction "DN2_B7") (pintype "bidirectional"))
    )
    (net (code "44") (name "Net-(R11-1)") (class "Default")
      (node (ref "R11") (pin "P$1") (pinfunction "1_P$1") (pintype "passive"))
      (node (ref "R13") (pin "P$2") (pinfunction "2_P$2") (pintype "passive"))
      (node (ref "U1") (pin "P$6") (pinfunction "TNOW_P$6") (pintype "passive"))
    )
    (net (code "45") (name "Net-(R12-1)") (class "Default")
      (node (ref "R12") (pin "P$1") (pinfunction "1_P$1") (pintype "passive"))
      (node (ref "U2") (pin "P$1") (pinfunction "RO_P$1") (pintype "passive"))
    )
    (net (code "46") (name "Net-(R12-2)") (class "Default")
      (node (ref "R12") (pin "P$2") (pinfunction "2_P$2") (pintype "passive"))
      (node (ref "U1") (pin "P$9") (pinfunction "RXD_P$9") (pintype "passive"))
    )
    (net (code "47") (name "Net-(R13-1)") (class "Default")
      (node (ref "R13") (pin "P$1") (pinfunction "1_P$1") (pintype "passive"))
      (node (ref "U2") (pin "P$2") (pinfunction "NRE_P$2") (pintype "passive"))
      (node (ref "U2") (pin "P$3") (pinfunction "DE_P$3") (pintype "passive"))
    )
    (net (code "48") (name "Net-(R14-1)") (class "Default")
      (node (ref "R14") (pin "P$1") (pinfunction "1_P$1") (pintype "passive"))
      (node (ref "U2") (pin "P$4") (pinfunction "DI_P$4") (pintype "passive"))
    )
    (net (code "49") (name "Net-(R14-2)") (class "Default")
      (node (ref "R14") (pin "P$2") (pinfunction "2_P$2") (pintype "passive"))
      (node (ref "U1") (pin "P$8") (pinfunction "TXD_P$8") (pintype "passive"))
    )
    (net (code "50") (name "Net-(R15-2)") (class "Default")
      (node (ref "R15") (pin "P$2") (pinfunction "2_P$2") (pintype "passive"))
      (node (ref "U4") (pin "P$21") (pinfunction "XOUT_P$21") (pintype "bidirectional"))
    )
    (net (code "51") (name "Net-(R16-2)") (class "Default")
      (node (ref "R16") (pin "P$2") (pinfunction "2_P$2") (pintype "passive"))
      (node (ref "R19") (pin "P$2") (pinfunction "2_P$2") (pintype "passive"))
      (node (ref "U2") (pin "P$7") (pinfunction "B_P$7") (pintype "passive"))
    )
    (net (code "52") (name "Net-(R17-2)") (class "Default")
      (node (ref "R17") (pin "P$2") (pinfunction "2_P$2") (pintype "passive"))
      (node (ref "R18") (pin "P$2") (pinfunction "2_P$2") (pintype "passive"))
      (node (ref "U2") (pin "P$6") (pinfunction "A_P$6") (pintype "passive"))
    )
    (net (code "53") (name "VDD") (class "Default")
      (node (ref "C19") (pin "P$2") (pinfunction "2_P$2") (pintype "passive"))
      (node (ref "CN10") (pin "3") (pinfunction "3_3") (pintype "bidirectional"))
      (node (ref "CN11") (pin "3") (pinfunction "3_3") (pintype "bidirectional"))
      (node (ref "CN12") (pin "3") (pinfunction "3_3") (pintype "bidirectional"))
      (node (ref "CN13") (pin "3") (pinfunction "3_3") (pintype "bidirectional"))
      (node (ref "R26") (pin "P$2") (pinfunction "2_P$2") (pintype "passive"))
      (node (ref "R27") (pin "P$2") (pinfunction "2_P$2") (pintype "passive"))
      (node (ref "R6") (pin "P$2") (pinfunction "2_P$2") (pintype "passive"))
      (node (ref "U6") (pin "P$1") (pinfunction "IN_P$1") (pintype "input"))
      (node (ref "U6") (pin "P$3") (pinfunction "CTRL_P$3") (pintype "input"))
    )
    (net (code "54") (name "unconnected-(CN5-Pad1)") (class "Default")
      (node (ref "CN5") (pin "1") (pinfunction "1_1") (pintype "bidirectional"))
    )
    (net (code "55") (name "unconnected-(CN6-Pad1)") (class "Default")
      (node (ref "CN6") (pin "1") (pinfunction "1_1") (pintype "bidirectional"))
    )
    (net (code "56") (name "unconnected-(CN7-Pad1)") (class "Default")
      (node (ref "CN7") (pin "1") (pinfunction "1_1") (pintype "bidirectional"))
    )
    (net (code "57") (name "unconnected-(CN8-Pad1)") (class "Default")
      (node (ref "CN8") (pin "1") (pinfunction "1_1") (pintype "bidirectional"))
    )
    (net (code "58") (name "unconnected-(U1-CTS#-PadP$5)") (class "Default")
      (node (ref "U1") (pin "P$5") (pinfunction "CTS#_P$5") (pintype "passive"))
    )
    (net (code "59") (name "unconnected-(U1-RTS#-PadP$4)") (class "Default")
      (node (ref "U1") (pin "P$4") (pinfunction "RTS#_P$4") (pintype "passive"))
    )
    (net (code "60") (name "unconnected-(U3-BOOT_LOAD-PadP$8)") (class "Default")
      (node (ref "U3") (pin "P$8") (pinfunction "BOOT_LOAD_P$8") (pintype "bidirectional"))
    )
    (net (code "61") (name "unconnected-(U4-GPIO0-PadP$2)") (class "Default")
      (node (ref "U4") (pin "P$2") (pinfunction "GPIO0_P$2") (pintype "bidirectional"))
    )
    (net (code "62") (name "unconnected-(U4-GPIO1-PadP$3)") (class "Default")
      (node (ref "U4") (pin "P$3") (pinfunction "GPIO1_P$3") (pintype "bidirectional"))
    )
    (net (code "63") (name "unconnected-(U4-GPIO2-PadP$4)") (class "Default")
      (node (ref "U4") (pin "P$4") (pinfunction "GPIO2_P$4") (pintype "bidirectional"))
    )
    (net (code "64") (name "unconnected-(U4-GPIO3-PadP$5)") (class "Default")
      (node (ref "U4") (pin "P$5") (pinfunction "GPIO3_P$5") (pintype "bidirectional"))
    )
    (net (code "65") (name "unconnected-(U4-GPIO6-PadP$8)") (class "Default")
      (node (ref "U4") (pin "P$8") (pinfunction "GPIO6_P$8") (pintype "bidirectional"))
    )
    (net (code "66") (name "unconnected-(U4-GPIO7-PadP$9)") (class "Default")
      (node (ref "U4") (pin "P$9") (pinfunction "GPIO7_P$9") (pintype "bidirectional"))
    )
    (net (code "67") (name "unconnected-(U4-GPIO10-PadP$13)") (class "Default")
      (node (ref "U4") (pin "P$13") (pinfunction "GPIO10_P$13") (pintype "bidirectional"))
    )
    (net (code "68") (name "unconnected-(U4-GPIO11-PadP$14)") (class "Default")
      (node (ref "U4") (pin "P$14") (pinfunction "GPIO11_P$14") (pintype "bidirectional"))
    )
    (net (code "69") (name "unconnected-(U4-GPIO12-PadP$15)") (class "Default")
      (node (ref "U4") (pin "P$15") (pinfunction "GPIO12_P$15") (pintype "bidirectional"))
    )
    (net (code "70") (name "unconnected-(U4-GPIO13-PadP$16)") (class "Default")
      (node (ref "U4") (pin "P$16") (pinfunction "GPIO13_P$16") (pintype "bidirectional"))
    )
    (net (code "71") (name "unconnected-(U4-GPIO14-PadP$17)") (class "Default")
      (node (ref "U4") (pin "P$17") (pinfunction "GPIO14_P$17") (pintype "bidirectional"))
    )
    (net (code "72") (name "unconnected-(U4-GPIO15-PadP$18)") (class "Default")
      (node (ref "U4") (pin "P$18") (pinfunction "GPIO15_P$18") (pintype "bidirectional"))
    )
    (net (code "73") (name "unconnected-(U4-GPIO16-PadP$27)") (class "Default")
      (node (ref "U4") (pin "P$27") (pinfunction "GPIO16_P$27") (pintype "bidirectional"))
    )
    (net (code "74") (name "unconnected-(U4-GPIO17-PadP$28)") (class "Default")
      (node (ref "U4") (pin "P$28") (pinfunction "GPIO17_P$28") (pintype "bidirectional"))
    )
    (net (code "75") (name "unconnected-(U4-GPIO20-PadP$31)") (class "Default")
      (node (ref "U4") (pin "P$31") (pinfunction "GPIO20_P$31") (pintype "bidirectional"))
    )
    (net (code "76") (name "unconnected-(U4-GPIO21-PadP$32)") (class "Default")
      (node (ref "U4") (pin "P$32") (pinfunction "GPIO21_P$32") (pintype "bidirectional"))
    )
    (net (code "77") (name "unconnected-(U4-GPIO22-PadP$34)") (class "Default")
      (node (ref "U4") (pin "P$34") (pinfunction "GPIO22_P$34") (pintype "bidirectional"))
    )
    (net (code "78") (name "unconnected-(U4-GPIO23-PadP$35)") (class "Default")
      (node (ref "U4") (pin "P$35") (pinfunction "GPIO23_P$35") (pintype "bidirectional"))
    )
    (net (code "79") (name "unconnected-(U4-GPIO24-PadP$36)") (class "Default")
      (node (ref "U4") (pin "P$36") (pinfunction "GPIO24_P$36") (pintype "bidirectional"))
    )
    (net (code "80") (name "unconnected-(U4-GPIO25-PadP$37)") (class "Default")
      (node (ref "U4") (pin "P$37") (pinfunction "GPIO25_P$37") (pintype "bidirectional"))
    )
    (net (code "81") (name "unconnected-(U4-GPIO26{slash}ADC0-PadP$38)") (class "Default")
      (node (ref "U4") (pin "P$38") (pinfunction "GPIO26/ADC0_P$38") (pintype "bidirectional"))
    )
    (net (code "82") (name "unconnected-(U4-GPIO27{slash}ADC1-PadP$39)") (class "Default")
      (node (ref "U4") (pin "P$39") (pinfunction "GPIO27/ADC1_P$39") (pintype "bidirectional"))
    )
    (net (code "83") (name "unconnected-(U4-GPIO28{slash}ADC2-PadP$40)") (class "Default")
      (node (ref "U4") (pin "P$40") (pinfunction "GPIO28/ADC2_P$40") (pintype "bidirectional"))
    )
    (net (code "84") (name "unconnected-(U4-GPIO29{slash}ADC3-PadP$41)") (class "Default")
      (node (ref "U4") (pin "P$41") (pinfunction "GPIO29/ADC3_P$41") (pintype "bidirectional"))
    )
    (net (code "85") (name "unconnected-(U4-SWCLK-PadP$24)") (class "Default")
      (node (ref "U4") (pin "P$24") (pinfunction "SWCLK_P$24") (pintype "bidirectional"))
    )
    (net (code "86") (name "unconnected-(U4-SWDIO-PadP$25)") (class "Default")
      (node (ref "U4") (pin "P$25") (pinfunction "SWDIO_P$25") (pintype "bidirectional"))
    )
    (net (code "87") (name "unconnected-(U6-CS-PadP$4)") (class "Default")
      (node (ref "U6") (pin "P$4") (pinfunction "CS_P$4") (pintype "passive"))
    )
    (net (code "88") (name "unconnected-(U7-NC-PadP$1)") (class "Default")
      (node (ref "U7") (pin "P$1") (pinfunction "NC_P$1") (pintype "passive"))
    )
    (net (code "89") (name "unconnected-(U8-VOUT-PadP$8)") (class "Default")
      (node (ref "U8") (pin "P$8") (pinfunction "VOUT_P$8") (pintype "passive"))
    )
    (net (code "90") (name "unconnected-(USB1-SBU1-PadA8)") (class "Default")
      (node (ref "USB1") (pin "A8") (pinfunction "SBU1_A8") (pintype "bidirectional"))
    )
    (net (code "91") (name "unconnected-(USB1-SBU2-PadB8)") (class "Default")
      (node (ref "USB1") (pin "B8") (pinfunction "SBU2_B8") (pintype "bidirectional"))
    )
    (net (code "92") (name "unconnected-(USB2-SBU1-PadA8)") (class "Default")
      (node (ref "USB2") (pin "A8") (pinfunction "SBU1_A8") (pintype "bidirectional"))
    )
    (net (code "93") (name "unconnected-(USB2-SBU2-PadB8)") (class "Default")
      (node (ref "USB2") (pin "B8") (pinfunction "SBU2_B8") (pintype "bidirectional"))
    )
  )
)
